# cn7macropad.net
KiCad netlist of a schematic drawn in EAGLE
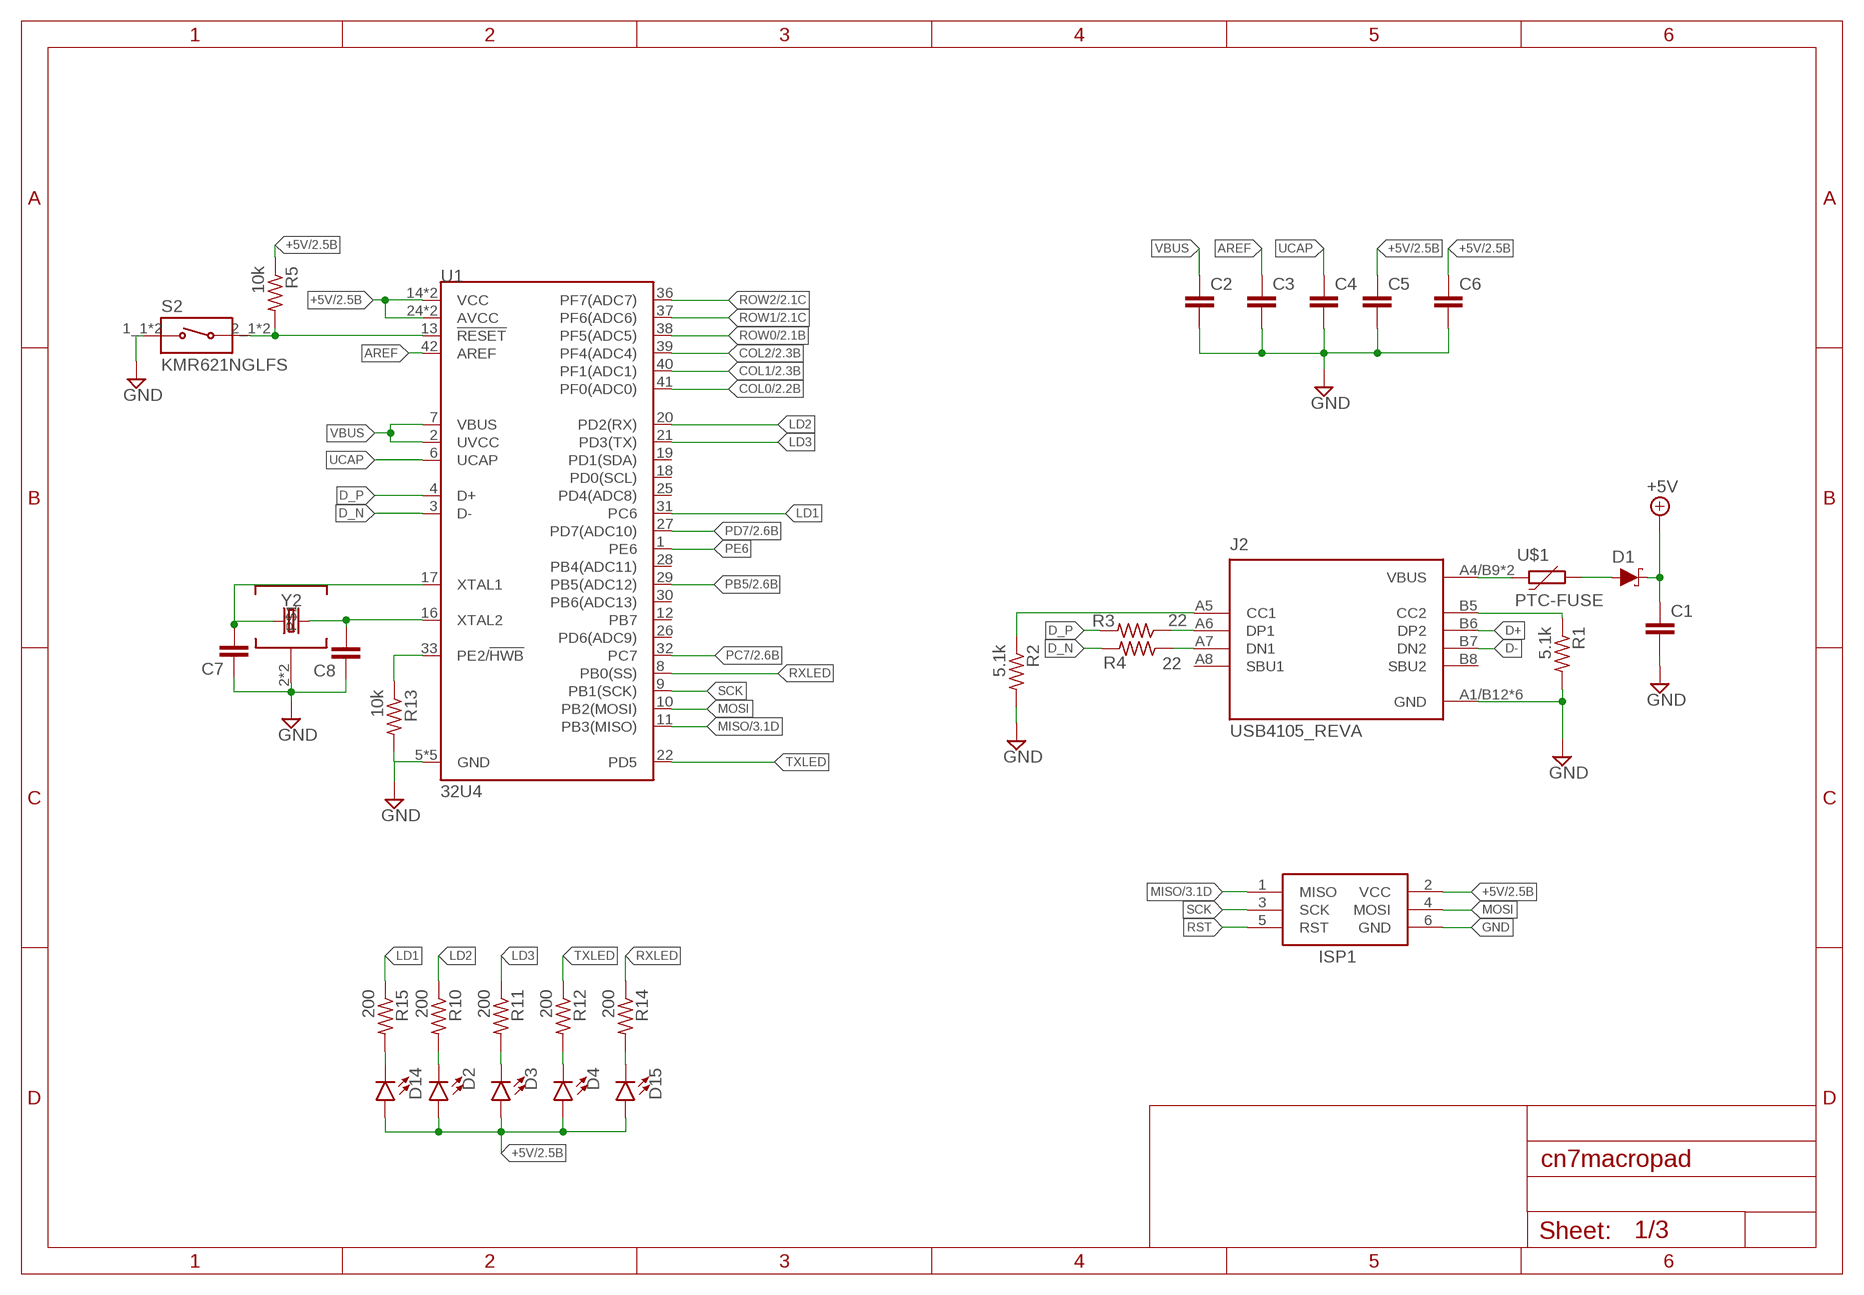
[diagram p0: schematic, sheet 1]
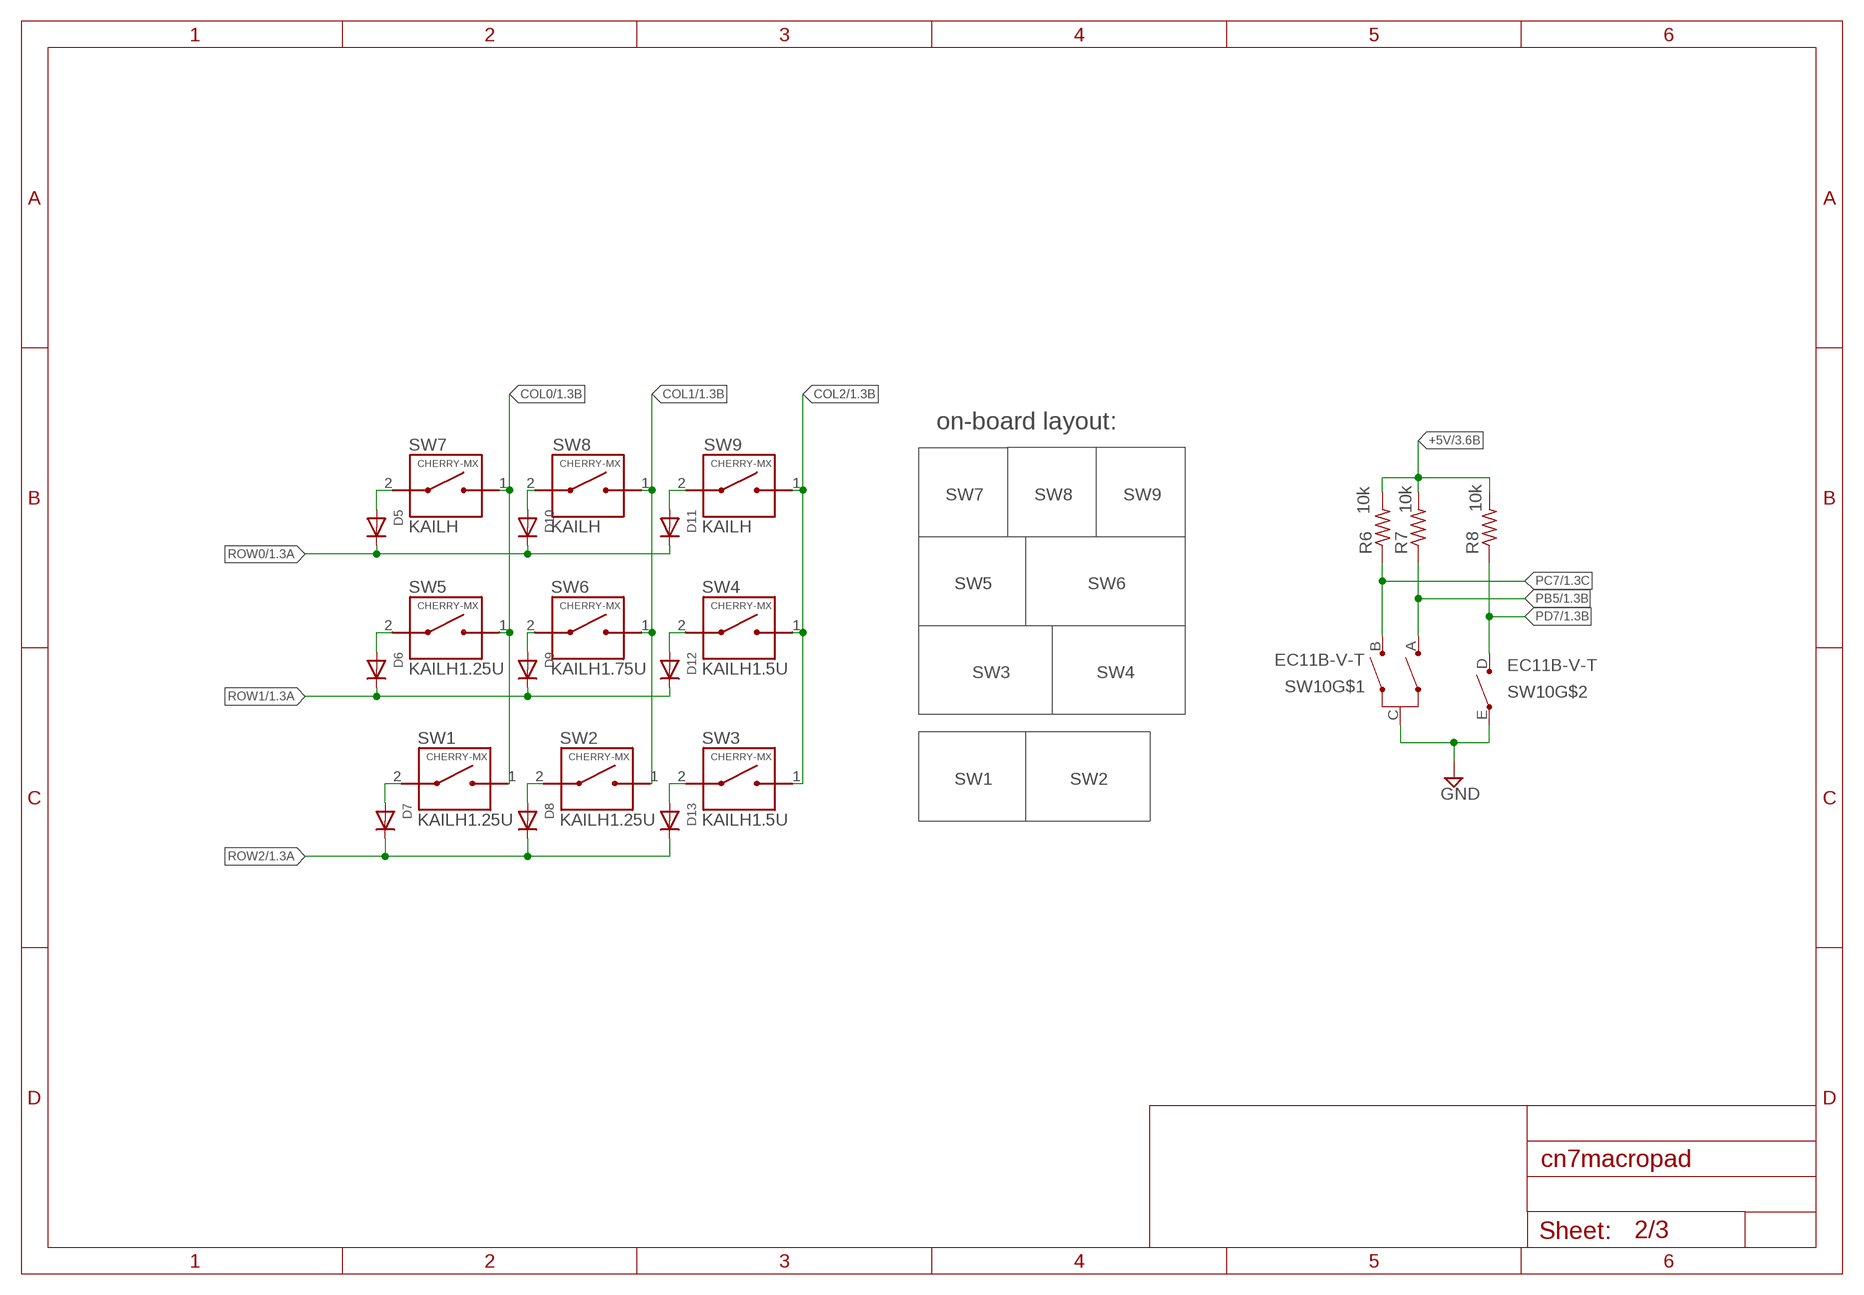
[diagram p1: schematic, sheet 2]
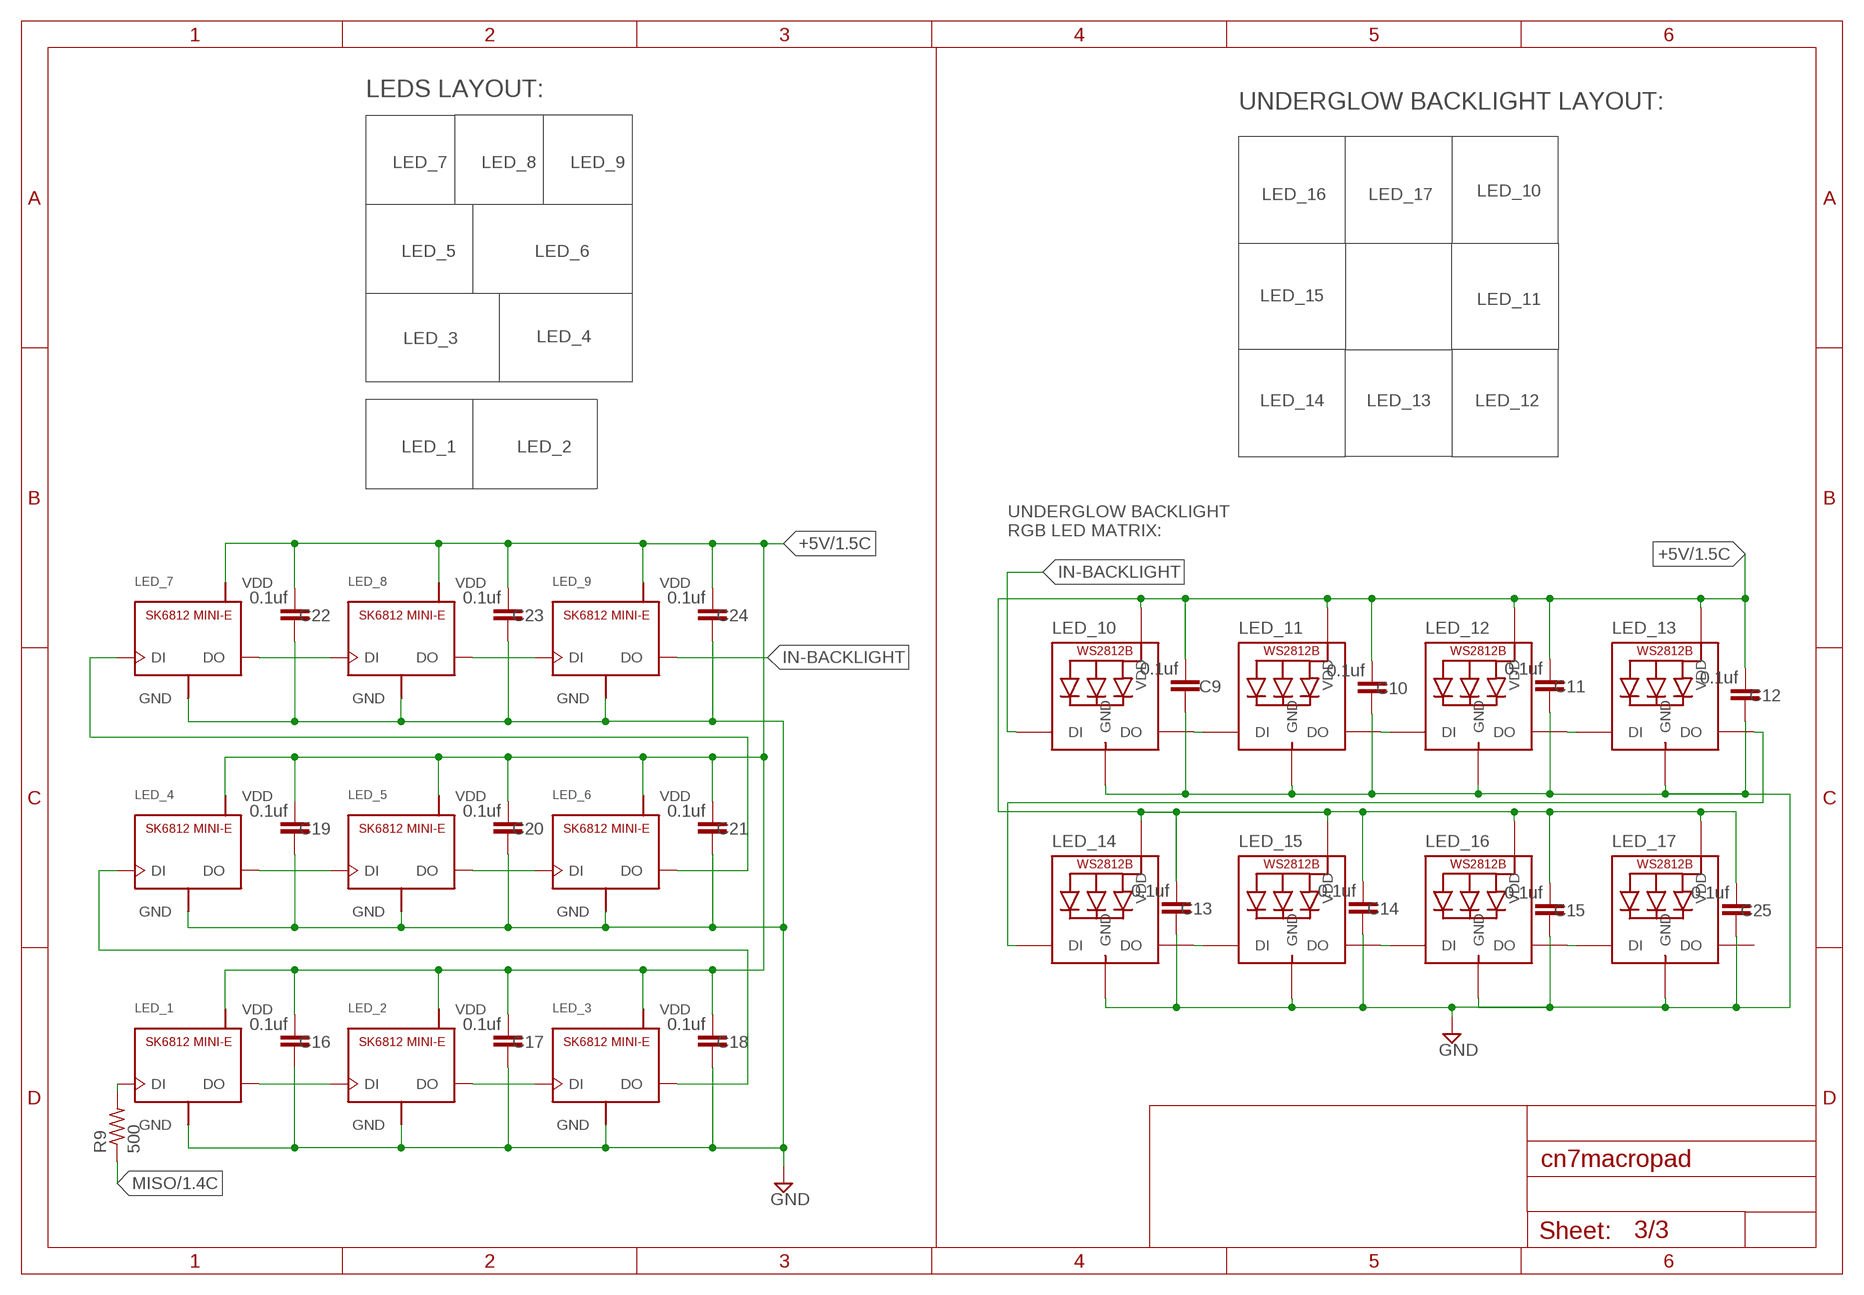
[diagram p2: schematic, sheet 3]

(export (version "E")
  (design (tool "Eeschema 10.0.6"))
  (components
    (comp (ref "C9")
      (value "0.1uf")
      (footprint "eagle-import:0603")
      (libsource (lib "eagle-import") (part "CAP-0603-50V-5%"))
    )
    (comp (ref "C10")
      (value "0.1uf")
      (footprint "eagle-import:0603")
      (libsource (lib "eagle-import") (part "CAP-0603-50V-5%"))
    )
    (comp (ref "C11")
      (value "0.1uf")
      (footprint "eagle-import:0603")
      (libsource (lib "eagle-import") (part "CAP-0603-50V-5%"))
    )
    (comp (ref "C12")
      (value "0.1uf")
      (footprint "eagle-import:0603")
      (libsource (lib "eagle-import") (part "CAP-0603-50V-5%"))
    )
    (comp (ref "C13")
      (value "0.1uf")
      (footprint "eagle-import:0603")
      (libsource (lib "eagle-import") (part "CAP-0603-50V-5%"))
    )
    (comp (ref "C14")
      (value "0.1uf")
      (footprint "eagle-import:0603")
      (libsource (lib "eagle-import") (part "CAP-0603-50V-5%"))
    )
    (comp (ref "C15")
      (value "0.1uf")
      (footprint "eagle-import:0603")
      (libsource (lib "eagle-import") (part "CAP-0603-50V-5%"))
    )
    (comp (ref "C16")
      (value "0.1uf")
      (footprint "eagle-import:0603")
      (libsource (lib "eagle-import") (part "CAP-0603-50V-5%"))
    )
    (comp (ref "C17")
      (value "0.1uf")
      (footprint "eagle-import:0603")
      (libsource (lib "eagle-import") (part "CAP-0603-50V-5%"))
    )
    (comp (ref "C18")
      (value "0.1uf")
      (footprint "eagle-import:0603")
      (libsource (lib "eagle-import") (part "CAP-0603-50V-5%"))
    )
    (comp (ref "C19")
      (value "0.1uf")
      (footprint "eagle-import:0603")
      (libsource (lib "eagle-import") (part "CAP-0603-50V-5%"))
    )
    (comp (ref "C20")
      (value "0.1uf")
      (footprint "eagle-import:0603")
      (libsource (lib "eagle-import") (part "CAP-0603-50V-5%"))
    )
    (comp (ref "C21")
      (value "0.1uf")
      (footprint "eagle-import:0603")
      (libsource (lib "eagle-import") (part "CAP-0603-50V-5%"))
    )
    (comp (ref "C22")
      (value "0.1uf")
      (footprint "eagle-import:0603")
      (libsource (lib "eagle-import") (part "CAP-0603-50V-5%"))
    )
    (comp (ref "C23")
      (value "0.1uf")
      (footprint "eagle-import:0603")
      (libsource (lib "eagle-import") (part "CAP-0603-50V-5%"))
    )
    (comp (ref "C24")
      (value "0.1uf")
      (footprint "eagle-import:0603")
      (libsource (lib "eagle-import") (part "CAP-0603-50V-5%"))
    )
    (comp (ref "C25")
      (value "0.1uf")
      (footprint "eagle-import:0603")
      (libsource (lib "eagle-import") (part "CAP-0603-50V-5%"))
    )
    (comp (ref "LED_1")
      (value "SK6812-MINI-ESW")
      (footprint "eagle-import:SK6812-MINI-E")
      (libsource (lib "eagle-import") (part "SK6812-MINI-ESW"))
    )
    (comp (ref "LED_2")
      (value "SK6812-MINI-ESW")
      (footprint "eagle-import:SK6812-MINI-E")
      (libsource (lib "eagle-import") (part "SK6812-MINI-ESW"))
    )
    (comp (ref "LED_3")
      (value "SK6812-MINI-ESW")
      (footprint "eagle-import:SK6812-MINI-E")
      (libsource (lib "eagle-import") (part "SK6812-MINI-ESW"))
    )
    (comp (ref "LED_4")
      (value "SK6812-MINI-ESW")
      (footprint "eagle-import:SK6812-MINI-E")
      (libsource (lib "eagle-import") (part "SK6812-MINI-ESW"))
    )
    (comp (ref "LED_5")
      (value "SK6812-MINI-ESW")
      (footprint "eagle-import:SK6812-MINI-E")
      (libsource (lib "eagle-import") (part "SK6812-MINI-ESW"))
    )
    (comp (ref "LED_6")
      (value "SK6812-MINI-ESW")
      (footprint "eagle-import:SK6812-MINI-E")
      (libsource (lib "eagle-import") (part "SK6812-MINI-ESW"))
    )
    (comp (ref "LED_7")
      (value "SK6812-MINI-ESW")
      (footprint "eagle-import:SK6812-MINI-E")
      (libsource (lib "eagle-import") (part "SK6812-MINI-ESW"))
    )
    (comp (ref "LED_8")
      (value "SK6812-MINI-ESW")
      (footprint "eagle-import:SK6812-MINI-E")
      (libsource (lib "eagle-import") (part "SK6812-MINI-ESW"))
    )
    (comp (ref "LED_9")
      (value "SK6812-MINI-ESW")
      (footprint "eagle-import:SK6812-MINI-E")
      (libsource (lib "eagle-import") (part "SK6812-MINI-ESW"))
    )
    (comp (ref "LED_10")
      (value "WS2812B5050")
      (footprint "eagle-import:WS2812B")
      (fields (field (name "SPICEPREFIX") "E"))
      (libsource (lib "eagle-import") (part "WS2812B5050"))
    )
    (comp (ref "LED_11")
      (value "WS2812B5050")
      (footprint "eagle-import:WS2812B")
      (libsource (lib "eagle-import") (part "WS2812B5050"))
    )
    (comp (ref "LED_12")
      (value "WS2812B5050")
      (footprint "eagle-import:WS2812B")
      (libsource (lib "eagle-import") (part "WS2812B5050"))
    )
    (comp (ref "LED_13")
      (value "WS2812B5050")
      (footprint "eagle-import:WS2812B")
      (libsource (lib "eagle-import") (part "WS2812B5050"))
    )
    (comp (ref "LED_14")
      (value "WS2812B5050")
      (footprint "eagle-import:WS2812B")
      (libsource (lib "eagle-import") (part "WS2812B5050"))
    )
    (comp (ref "LED_15")
      (value "WS2812B5050")
      (footprint "eagle-import:WS2812B")
      (libsource (lib "eagle-import") (part "WS2812B5050"))
    )
    (comp (ref "LED_16")
      (value "WS2812B5050")
      (footprint "eagle-import:WS2812B")
      (libsource (lib "eagle-import") (part "WS2812B5050"))
    )
    (comp (ref "LED_17")
      (value "WS2812B5050")
      (footprint "eagle-import:WS2812B")
      (libsource (lib "eagle-import") (part "WS2812B5050"))
    )
    (comp (ref "R9")
      (value "500")
      (footprint "eagle-import:R0603")
      (libsource (lib "eagle-import") (part "RESISTORR0603"))
    )
    (comp (ref "D5")
      (value "DIODE")
      (footprint "eagle-import:SOD-523")
      (libsource (lib "eagle-import") (part "DIODE"))
    )
    (comp (ref "D6")
      (value "DIODE")
      (footprint "eagle-import:SOD-523")
      (libsource (lib "eagle-import") (part "DIODE"))
    )
    (comp (ref "D7")
      (value "DIODE")
      (footprint "eagle-import:SOD-523")
      (libsource (lib "eagle-import") (part "DIODE"))
    )
    (comp (ref "D8")
      (value "DIODE")
      (footprint "eagle-import:SOD-523")
      (libsource (lib "eagle-import") (part "DIODE"))
    )
    (comp (ref "D9")
      (value "DIODE")
      (footprint "eagle-import:SOD-523")
      (libsource (lib "eagle-import") (part "DIODE"))
    )
    (comp (ref "D10")
      (value "DIODE")
      (footprint "eagle-import:SOD-523")
      (libsource (lib "eagle-import") (part "DIODE"))
    )
    (comp (ref "D11")
      (value "DIODE")
      (footprint "eagle-import:SOD-523")
      (libsource (lib "eagle-import") (part "DIODE"))
    )
    (comp (ref "D12")
      (value "DIODESOD-523")
      (footprint "eagle-import:SOD-523")
      (libsource (lib "eagle-import") (part "DIODESOD-523"))
    )
    (comp (ref "D13")
      (value "DIODESOD-523")
      (footprint "eagle-import:SOD-523")
      (libsource (lib "eagle-import") (part "DIODESOD-523"))
    )
    (comp (ref "R6")
      (value "10k")
      (footprint "eagle-import:R0603")
      (libsource (lib "eagle-import") (part "RESISTORR0603"))
    )
    (comp (ref "R7")
      (value "10k")
      (footprint "eagle-import:R0603")
      (libsource (lib "eagle-import") (part "RESISTORR0603"))
    )
    (comp (ref "R8")
      (value "10k")
      (footprint "eagle-import:R0603")
      (libsource (lib "eagle-import") (part "RESISTORR0603"))
    )
    (comp (ref "SW1")
      (value "KAILH1.25U")
      (footprint "eagle-import:SWITCH_SOCKET-1.25U")
      (libsource (lib "eagle-import") (part "KAILH1.25U"))
    )
    (comp (ref "SW2")
      (value "KAILH1.25U")
      (footprint "eagle-import:SWITCH_SOCKET-1.25U")
      (libsource (lib "eagle-import") (part "KAILH1.25U"))
    )
    (comp (ref "SW3")
      (value "KAILH1.5U")
      (footprint "eagle-import:SWITCH_SOCKET-1.5U")
      (libsource (lib "eagle-import") (part "KAILH1.5U"))
    )
    (comp (ref "SW4")
      (value "KAILH1.5U")
      (footprint "eagle-import:SWITCH_SOCKET-1.5U")
      (libsource (lib "eagle-import") (part "KAILH1.5U"))
    )
    (comp (ref "SW5")
      (value "KAILH1.25U")
      (footprint "eagle-import:SWITCH_SOCKET-1.25U")
      (libsource (lib "eagle-import") (part "KAILH1.25U"))
    )
    (comp (ref "SW6")
      (value "KAILH1.75U")
      (footprint "eagle-import:SWITCH_SOCKET-1.75U")
      (libsource (lib "eagle-import") (part "KAILH1.75U"))
    )
    (comp (ref "SW7")
      (value "KAILH")
      (footprint "eagle-import:SWITCH_SOCKET-1U")
      (libsource (lib "eagle-import") (part "KAILH"))
    )
    (comp (ref "SW8")
      (value "KAILH")
      (footprint "eagle-import:SWITCH_SOCKET-1U")
      (libsource (lib "eagle-import") (part "KAILH"))
    )
    (comp (ref "SW9")
      (value "KAILH")
      (footprint "eagle-import:SWITCH_SOCKET-1U")
      (libsource (lib "eagle-import") (part "KAILH"))
    )
    (comp (ref "SW10")
      (value "EC11B-V-T")
      (footprint "eagle-import:EC11B-V")
      (libsource (lib "eagle-import") (part "EC11B-V-T"))
    )
    (comp (ref "C1")
      (value "10uF")
      (footprint "eagle-import:0603")
      (libsource (lib "eagle-import") (part "CAP-0603-50V-5%"))
    )
    (comp (ref "C2")
      (value "1.0uF")
      (footprint "eagle-import:0603")
      (libsource (lib "eagle-import") (part "CAP-0603-50V-5%"))
    )
    (comp (ref "C3")
      (value "1.0uF")
      (footprint "eagle-import:0603")
      (libsource (lib "eagle-import") (part "CAP-0603-50V-5%"))
    )
    (comp (ref "C4")
      (value "1.0uF")
      (footprint "eagle-import:0603")
      (libsource (lib "eagle-import") (part "CAP-0603-50V-5%"))
    )
    (comp (ref "C5")
      (value "1.0uF")
      (footprint "eagle-import:0603")
      (libsource (lib "eagle-import") (part "CAP-0603-50V-5%"))
    )
    (comp (ref "C6")
      (value "1.0uF")
      (footprint "eagle-import:0603")
      (libsource (lib "eagle-import") (part "CAP-0603-50V-5%"))
    )
    (comp (ref "C7")
      (value "22pF")
      (footprint "eagle-import:0603")
      (libsource (lib "eagle-import") (part "CAP-0603-50V-5%"))
    )
    (comp (ref "C8")
      (value "22pF")
      (footprint "eagle-import:0603")
      (libsource (lib "eagle-import") (part "CAP-0603-50V-5%"))
    )
    (comp (ref "D1")
      (value "3A/10V/280mV")
      (footprint "eagle-import:SOD-323")
      (libsource (lib "eagle-import") (part "DIODE-SCHOTTKY-BAT60A"))
    )
    (comp (ref "D2")
      (value "LED0603")
      (footprint "eagle-import:LED-0603")
      (libsource (lib "eagle-import") (part "LED0603"))
    )
    (comp (ref "D3")
      (value "LED0603")
      (footprint "eagle-import:LED-0603")
      (libsource (lib "eagle-import") (part "kailh_cn7_LED0603"))
    )
    (comp (ref "D4")
      (value "LED0603")
      (footprint "eagle-import:LED-0603")
      (libsource (lib "eagle-import") (part "kailh_cn7_LED0603"))
    )
    (comp (ref "D14")
      (value "LED0603")
      (footprint "eagle-import:LED-0603")
      (libsource (lib "eagle-import") (part "kailh_cn7_LED0603"))
    )
    (comp (ref "D15")
      (value "LED0603")
      (footprint "eagle-import:LED-0603")
      (libsource (lib "eagle-import") (part "kailh_cn7_LED0603"))
    )
    (comp (ref "ISP1")
      (value "AVRISP-6")
      (footprint "eagle-import:AVRISP")
      (libsource (lib "eagle-import") (part "AVRISP-6"))
    )
    (comp (ref "J2")
      (value "USB4105_REVA")
      (footprint "eagle-import:GCT_USB4105_REVA")
      (fields
        (field (name "DIGI-KEY_PART_NUMBER") "2073-USB4105-GF-ACT-ND")
        (field (name "MF") "Global Connector Technology")
        (field (name "MP") "USB4105")
      )
      (libsource (lib "eagle-import") (part "USB4105_REVA"))
    )
    (comp (ref "R1")
      (value "5.1k")
      (footprint "eagle-import:R0603")
      (libsource (lib "eagle-import") (part "RESISTORR0603"))
    )
    (comp (ref "R2")
      (value "5.1k")
      (footprint "eagle-import:R0603")
      (libsource (lib "eagle-import") (part "RESISTORR0603"))
    )
    (comp (ref "R3")
      (value "22")
      (footprint "eagle-import:R0603")
      (libsource (lib "eagle-import") (part "RESISTORR0603"))
    )
    (comp (ref "R4")
      (value "22")
      (footprint "eagle-import:R0603")
      (libsource (lib "eagle-import") (part "RESISTORR0603"))
    )
    (comp (ref "R5")
      (value "10k")
      (footprint "eagle-import:R0603")
      (libsource (lib "eagle-import") (part "RESISTORR0603"))
    )
    (comp (ref "R10")
      (value "200")
      (footprint "eagle-import:R0603")
      (libsource (lib "eagle-import") (part "RESISTORR0603"))
    )
    (comp (ref "R11")
      (value "200")
      (footprint "eagle-import:R0603")
      (libsource (lib "eagle-import") (part "RESISTORR0603"))
    )
    (comp (ref "R12")
      (value "200")
      (footprint "eagle-import:R0603")
      (libsource (lib "eagle-import") (part "RESISTORR0603"))
    )
    (comp (ref "R13")
      (value "10k")
      (footprint "eagle-import:R0603")
      (libsource (lib "eagle-import") (part "RESISTORR0603"))
    )
    (comp (ref "R14")
      (value "200")
      (footprint "eagle-import:R0603")
      (libsource (lib "eagle-import") (part "RESISTORR0603"))
    )
    (comp (ref "R15")
      (value "200")
      (footprint "eagle-import:R0603")
      (libsource (lib "eagle-import") (part "RESISTORR0603"))
    )
    (comp (ref "S2")
      (value "KMR621NGLFS")
      (footprint "eagle-import:SW_KMR621NGLFS")
      (fields
        (field (name "DIGI-KEY_PART_NUMBER") "CKN10684CT-ND")
        (field (name "MF") "C&K")
        (field (name "MP") "KMR621NG LFS")
      )
      (libsource (lib "eagle-import") (part "KMR621NGLFS"))
    )
    (comp (ref "U$1")
      (value "PTC-FUSE")
      (footprint "eagle-import:PTC1206")
      (libsource (lib "eagle-import") (part "PTC-FUSE"))
    )
    (comp (ref "U1")
      (value "32U4")
      (footprint "eagle-import:TQFP44")
      (libsource (lib "eagle-import") (part "ATMEGA32U4TQFP-44"))
    )
    (comp (ref "Y2")
      (value "CRYSTALSMD-3.2X2.5")
      (footprint "eagle-import:CRYSTAL-SMD-3.2X2.5MM")
      (libsource (lib "eagle-import") (part "CRYSTALSMD-3.2X2.5"))
    )
  )
  (nets
    (net (code "1") (name "+5V") (class "Default")
      (node (ref "C1") (pin "1") (pinfunction "1_1") (pintype "passive"))
      (node (ref "C10") (pin "2") (pinfunction "2_2") (pintype "passive"))
      (node (ref "C11") (pin "2") (pinfunction "2_2") (pintype "passive"))
      (node (ref "C12") (pin "2") (pinfunction "2_2") (pintype "passive"))
      (node (ref "C13") (pin "2") (pinfunction "2_2") (pintype "passive"))
      (node (ref "C14") (pin "2") (pinfunction "2_2") (pintype "passive"))
      (node (ref "C15") (pin "2") (pinfunction "2_2") (pintype "passive"))
      (node (ref "C16") (pin "2") (pinfunction "2_2") (pintype "passive"))
      (node (ref "C17") (pin "2") (pinfunction "2_2") (pintype "passive"))
      (node (ref "C18") (pin "2") (pinfunction "2_2") (pintype "passive"))
      (node (ref "C19") (pin "2") (pinfunction "2_2") (pintype "passive"))
      (node (ref "C20") (pin "2") (pinfunction "2_2") (pintype "passive"))
      (node (ref "C21") (pin "2") (pinfunction "2_2") (pintype "passive"))
      (node (ref "C22") (pin "2") (pinfunction "2_2") (pintype "passive"))
      (node (ref "C23") (pin "2") (pinfunction "2_2") (pintype "passive"))
      (node (ref "C24") (pin "2") (pinfunction "2_2") (pintype "passive"))
      (node (ref "C25") (pin "2") (pinfunction "2_2") (pintype "passive"))
      (node (ref "C5") (pin "1") (pinfunction "1_1") (pintype "passive"))
      (node (ref "C6") (pin "1") (pinfunction "1_1") (pintype "passive"))
      (node (ref "C9") (pin "2") (pinfunction "2_2") (pintype "passive"))
      (node (ref "D1") (pin "C") (pinfunction "C_C") (pintype "passive"))
      (node (ref "D14") (pin "A") (pinfunction "A_A") (pintype "passive"))
      (node (ref "D15") (pin "A") (pinfunction "A_A") (pintype "passive"))
      (node (ref "D2") (pin "A") (pinfunction "A_A") (pintype "passive"))
      (node (ref "D3") (pin "A") (pinfunction "A_A") (pintype "passive"))
      (node (ref "D4") (pin "A") (pinfunction "A_A") (pintype "passive"))
      (node (ref "ISP1") (pin "2") (pinfunction "VCC_2") (pintype "power_in"))
      (node (ref "LED_1") (pin "1-VDD") (pinfunction "VDD_1-VDD") (pintype "power_in"))
      (node (ref "LED_10") (pin "1-VDD") (pinfunction "VDD_1-VDD") (pintype "power_in"))
      (node (ref "LED_11") (pin "1-VDD") (pinfunction "VDD_1-VDD") (pintype "power_in"))
      (node (ref "LED_12") (pin "1-VDD") (pinfunction "VDD_1-VDD") (pintype "power_in"))
      (node (ref "LED_13") (pin "1-VDD") (pinfunction "VDD_1-VDD") (pintype "power_in"))
      (node (ref "LED_14") (pin "1-VDD") (pinfunction "VDD_1-VDD") (pintype "power_in"))
      (node (ref "LED_15") (pin "1-VDD") (pinfunction "VDD_1-VDD") (pintype "power_in"))
      (node (ref "LED_16") (pin "1-VDD") (pinfunction "VDD_1-VDD") (pintype "power_in"))
      (node (ref "LED_17") (pin "1-VDD") (pinfunction "VDD_1-VDD") (pintype "power_in"))
      (node (ref "LED_2") (pin "1-VDD") (pinfunction "VDD_1-VDD") (pintype "power_in"))
      (node (ref "LED_3") (pin "1-VDD") (pinfunction "VDD_1-VDD") (pintype "power_in"))
      (node (ref "LED_4") (pin "1-VDD") (pinfunction "VDD_1-VDD") (pintype "power_in"))
      (node (ref "LED_5") (pin "1-VDD") (pinfunction "VDD_1-VDD") (pintype "power_in"))
      (node (ref "LED_6") (pin "1-VDD") (pinfunction "VDD_1-VDD") (pintype "power_in"))
      (node (ref "LED_7") (pin "1-VDD") (pinfunction "VDD_1-VDD") (pintype "power_in"))
      (node (ref "LED_8") (pin "1-VDD") (pinfunction "VDD_1-VDD") (pintype "power_in"))
      (node (ref "LED_9") (pin "1-VDD") (pinfunction "VDD_1-VDD") (pintype "power_in"))
      (node (ref "R5") (pin "1") (pinfunction "1_1") (pintype "passive"))
      (node (ref "R6") (pin "2") (pinfunction "2_2") (pintype "passive"))
      (node (ref "R7") (pin "2") (pinfunction "2_2") (pintype "passive"))
      (node (ref "R8") (pin "2") (pinfunction "2_2") (pintype "passive"))
      (node (ref "U1") (pin "14") (pinfunction "VCC_14") (pintype "bidirectional"))
      (node (ref "U1") (pin "24") (pinfunction "AVCC_24") (pintype "bidirectional"))
      (node (ref "U1") (pin "34") (pinfunction "VCC_34") (pintype "bidirectional"))
      (node (ref "U1") (pin "44") (pinfunction "AVCC_44") (pintype "bidirectional"))
    )
    (net (code "2") (name "AREF") (class "Default")
      (node (ref "C3") (pin "1") (pinfunction "1_1") (pintype "passive"))
      (node (ref "U1") (pin "42") (pinfunction "AREF_42") (pintype "bidirectional"))
    )
    (net (code "3") (name "COL0") (class "Default")
      (node (ref "SW1") (pin "1") (pinfunction "2_1") (pintype "passive"))
      (node (ref "SW5") (pin "1") (pinfunction "2_1") (pintype "passive"))
      (node (ref "SW7") (pin "1") (pinfunction "2_1") (pintype "passive"))
      (node (ref "U1") (pin "41") (pinfunction "PF0(ADC0)_41") (pintype "bidirectional"))
    )
    (net (code "4") (name "COL1") (class "Default")
      (node (ref "SW2") (pin "1") (pinfunction "2_1") (pintype "passive"))
      (node (ref "SW6") (pin "1") (pinfunction "2_1") (pintype "passive"))
      (node (ref "SW8") (pin "1") (pinfunction "2_1") (pintype "passive"))
      (node (ref "U1") (pin "40") (pinfunction "PF1(ADC1)_40") (pintype "bidirectional"))
    )
    (net (code "5") (name "COL2") (class "Default")
      (node (ref "SW3") (pin "1") (pinfunction "2_1") (pintype "passive"))
      (node (ref "SW4") (pin "1") (pinfunction "2_1") (pintype "passive"))
      (node (ref "SW9") (pin "1") (pinfunction "2_1") (pintype "passive"))
      (node (ref "U1") (pin "39") (pinfunction "PF4(ADC4)_39") (pintype "bidirectional"))
    )
    (net (code "6") (name "D+") (class "Default")
      (node (ref "J2") (pin "A6") (pinfunction "DP1_A6") (pintype "bidirectional"))
      (node (ref "J2") (pin "B6") (pinfunction "DP2_B6") (pintype "bidirectional"))
      (node (ref "R3") (pin "1") (pinfunction "1_1") (pintype "passive"))
    )
    (net (code "7") (name "D-") (class "Default")
      (node (ref "J2") (pin "A7") (pinfunction "DN1_A7") (pintype "bidirectional"))
      (node (ref "J2") (pin "B7") (pinfunction "DN2_B7") (pintype "bidirectional"))
      (node (ref "R4") (pin "1") (pinfunction "1_1") (pintype "passive"))
    )
    (net (code "8") (name "D_N") (class "Default")
      (node (ref "R4") (pin "2") (pinfunction "2_2") (pintype "passive"))
      (node (ref "U1") (pin "3") (pinfunction "D-_3") (pintype "bidirectional"))
    )
    (net (code "9") (name "D_P") (class "Default")
      (node (ref "R3") (pin "2") (pinfunction "2_2") (pintype "passive"))
      (node (ref "U1") (pin "4") (pinfunction "D+_4") (pintype "bidirectional"))
    )
    (net (code "10") (name "GND") (class "Default")
      (node (ref "C1") (pin "2") (pinfunction "2_2") (pintype "passive"))
      (node (ref "C10") (pin "1") (pinfunction "1_1") (pintype "passive"))
      (node (ref "C11") (pin "1") (pinfunction "1_1") (pintype "passive"))
      (node (ref "C12") (pin "1") (pinfunction "1_1") (pintype "passive"))
      (node (ref "C13") (pin "1") (pinfunction "1_1") (pintype "passive"))
      (node (ref "C14") (pin "1") (pinfunction "1_1") (pintype "passive"))
      (node (ref "C15") (pin "1") (pinfunction "1_1") (pintype "passive"))
      (node (ref "C16") (pin "1") (pinfunction "1_1") (pintype "passive"))
      (node (ref "C17") (pin "1") (pinfunction "1_1") (pintype "passive"))
      (node (ref "C18") (pin "1") (pinfunction "1_1") (pintype "passive"))
      (node (ref "C19") (pin "1") (pinfunction "1_1") (pintype "passive"))
      (node (ref "C2") (pin "2") (pinfunction "2_2") (pintype "passive"))
      (node (ref "C20") (pin "1") (pinfunction "1_1") (pintype "passive"))
      (node (ref "C21") (pin "1") (pinfunction "1_1") (pintype "passive"))
      (node (ref "C22") (pin "1") (pinfunction "1_1") (pintype "passive"))
      (node (ref "C23") (pin "1") (pinfunction "1_1") (pintype "passive"))
      (node (ref "C24") (pin "1") (pinfunction "1_1") (pintype "passive"))
      (node (ref "C25") (pin "1") (pinfunction "1_1") (pintype "passive"))
      (node (ref "C3") (pin "2") (pinfunction "2_2") (pintype "passive"))
      (node (ref "C4") (pin "2") (pinfunction "2_2") (pintype "passive"))
      (node (ref "C5") (pin "2") (pinfunction "2_2") (pintype "passive"))
      (node (ref "C6") (pin "2") (pinfunction "2_2") (pintype "passive"))
      (node (ref "C7") (pin "1") (pinfunction "1_1") (pintype "passive"))
      (node (ref "C8") (pin "1") (pinfunction "1_1") (pintype "passive"))
      (node (ref "C9") (pin "1") (pinfunction "1_1") (pintype "passive"))
      (node (ref "ISP1") (pin "6") (pinfunction "GND_6") (pintype "power_in"))
      (node (ref "J2") (pin "A1/B12") (pinfunction "GND_A1/B12") (pintype "power_in"))
      (node (ref "J2") (pin "B1/A12") (pinfunction "GND_B1/A12") (pintype "power_in"))
      (node (ref "J2") (pin "G1") (pinfunction "GND_G1") (pintype "power_in"))
      (node (ref "J2") (pin "G2") (pinfunction "GND_G2") (pintype "power_in"))
      (node (ref "J2") (pin "G3") (pinfunction "GND_G3") (pintype "power_in"))
      (node (ref "J2") (pin "G4") (pinfunction "GND_G4") (pintype "power_in"))
      (node (ref "LED_1") (pin "3-GND") (pinfunction "GND_3-GND") (pintype "power_in"))
      (node (ref "LED_10") (pin "3-GND") (pinfunction "GND_3-GND") (pintype "power_in"))
      (node (ref "LED_11") (pin "3-GND") (pinfunction "GND_3-GND") (pintype "power_in"))
      (node (ref "LED_12") (pin "3-GND") (pinfunction "GND_3-GND") (pintype "power_in"))
      (node (ref "LED_13") (pin "3-GND") (pinfunction "GND_3-GND") (pintype "power_in"))
      (node (ref "LED_14") (pin "3-GND") (pinfunction "GND_3-GND") (pintype "power_in"))
      (node (ref "LED_15") (pin "3-GND") (pinfunction "GND_3-GND") (pintype "power_in"))
      (node (ref "LED_16") (pin "3-GND") (pinfunction "GND_3-GND") (pintype "power_in"))
      (node (ref "LED_17") (pin "3-GND") (pinfunction "GND_3-GND") (pintype "power_in"))
      (node (ref "LED_2") (pin "3-GND") (pinfunction "GND_3-GND") (pintype "power_in"))
      (node (ref "LED_3") (pin "3-GND") (pinfunction "GND_3-GND") (pintype "power_in"))
      (node (ref "LED_4") (pin "3-GND") (pinfunction "GND_3-GND") (pintype "power_in"))
      (node (ref "LED_5") (pin "3-GND") (pinfunction "GND_3-GND") (pintype "power_in"))
      (node (ref "LED_6") (pin "3-GND") (pinfunction "GND_3-GND") (pintype "power_in"))
      (node (ref "LED_7") (pin "3-GND") (pinfunction "GND_3-GND") (pintype "power_in"))
      (node (ref "LED_8") (pin "3-GND") (pinfunction "GND_3-GND") (pintype "power_in"))
      (node (ref "LED_9") (pin "3-GND") (pinfunction "GND_3-GND") (pintype "power_in"))
      (node (ref "R1") (pin "2") (pinfunction "2_2") (pintype "passive"))
      (node (ref "R13") (pin "2") (pinfunction "2_2") (pintype "passive"))
      (node (ref "R2") (pin "2") (pinfunction "2_2") (pintype "passive"))
      (node (ref "S2") (pin "1_1") (pinfunction "1_1_1") (pintype "passive"))
      (node (ref "S2") (pin "1_2") (pinfunction "1_1_2") (pintype "passive"))
      (node (ref "SW10") (pin "C") (pinfunction "C_C") (pintype "passive"))
      (node (ref "SW10") (pin "E") (pinfunction "E_E") (pintype "passive"))
      (node (ref "U1") (pin "15") (pinfunction "GND_15") (pintype "bidirectional"))
      (node (ref "U1") (pin "23") (pinfunction "GND_23") (pintype "bidirectional"))
      (node (ref "U1") (pin "35") (pinfunction "GND_35") (pintype "bidirectional"))
      (node (ref "U1") (pin "43") (pinfunction "GND_43") (pintype "bidirectional"))
      (node (ref "U1") (pin "5") (pinfunction "GND_5") (pintype "bidirectional"))
      (node (ref "Y2") (pin "2") (pinfunction "P$1_2") (pintype "bidirectional"))
      (node (ref "Y2") (pin "4") (pinfunction "P$1_4") (pintype "bidirectional"))
    )
    (net (code "11") (name "IN-BACKLIGHT") (class "Default")
      (node (ref "LED_10") (pin "4-DIN") (pinfunction "DI_4-DIN") (pintype "input"))
      (node (ref "LED_9") (pin "2-DOUT") (pinfunction "DO_2-DOUT") (pintype "output"))
    )
    (net (code "12") (name "LD1") (class "Default")
      (node (ref "R15") (pin "1") (pinfunction "1_1") (pintype "passive"))
      (node (ref "U1") (pin "31") (pinfunction "PC6_31") (pintype "bidirectional"))
    )
    (net (code "13") (name "LD2") (class "Default")
      (node (ref "R10") (pin "1") (pinfunction "1_1") (pintype "passive"))
      (node (ref "U1") (pin "20") (pinfunction "PD2(RX)_20") (pintype "bidirectional"))
    )
    (net (code "14") (name "LD3") (class "Default")
      (node (ref "R11") (pin "1") (pinfunction "1_1") (pintype "passive"))
      (node (ref "U1") (pin "21") (pinfunction "PD3(TX)_21") (pintype "bidirectional"))
    )
    (net (code "15") (name "MISO") (class "Default")
      (node (ref "ISP1") (pin "1") (pinfunction "MISO_1") (pintype "input"))
      (node (ref "R9") (pin "1") (pinfunction "1_1") (pintype "passive"))
      (node (ref "U1") (pin "11") (pinfunction "PB3(MISO)_11") (pintype "bidirectional"))
    )
    (net (code "16") (name "MOSI") (class "Default")
      (node (ref "ISP1") (pin "4") (pinfunction "MOSI_4") (pintype "output"))
      (node (ref "U1") (pin "10") (pinfunction "PB2(MOSI)_10") (pintype "bidirectional"))
    )
    (net (code "17") (name "Net-(D1-PadA)") (class "Default")
      (node (ref "D1") (pin "A") (pinfunction "A_A") (pintype "passive"))
      (node (ref "U$1") (pin "2") (pinfunction "2_2") (pintype "passive"))
    )
    (net (code "18") (name "Net-(D2-PadC)") (class "Default")
      (node (ref "D2") (pin "C") (pinfunction "C_C") (pintype "passive"))
      (node (ref "R10") (pin "2") (pinfunction "2_2") (pintype "passive"))
    )
    (net (code "19") (name "Net-(D3-PadC)") (class "Default")
      (node (ref "D3") (pin "C") (pinfunction "C_C") (pintype "passive"))
      (node (ref "R11") (pin "2") (pinfunction "2_2") (pintype "passive"))
    )
    (net (code "20") (name "Net-(D4-PadC)") (class "Default")
      (node (ref "D4") (pin "C") (pinfunction "C_C") (pintype "passive"))
      (node (ref "R12") (pin "2") (pinfunction "2_2") (pintype "passive"))
    )
    (net (code "21") (name "Net-(D14-PadC)") (class "Default")
      (node (ref "D14") (pin "C") (pinfunction "C_C") (pintype "passive"))
      (node (ref "R15") (pin "2") (pinfunction "2_2") (pintype "passive"))
    )
    (net (code "22") (name "Net-(D15-PadC)") (class "Default")
      (node (ref "D15") (pin "C") (pinfunction "C_C") (pintype "passive"))
      (node (ref "R14") (pin "2") (pinfunction "2_2") (pintype "passive"))
    )
    (net (code "23") (name "Net-(J2-CC1)") (class "Default")
      (node (ref "J2") (pin "A5") (pinfunction "CC1_A5") (pintype "bidirectional"))
      (node (ref "R2") (pin "1") (pinfunction "1_1") (pintype "passive"))
    )
    (net (code "24") (name "Net-(J2-CC2)") (class "Default")
      (node (ref "J2") (pin "B5") (pinfunction "CC2_B5") (pintype "bidirectional"))
      (node (ref "R1") (pin "1") (pinfunction "1_1") (pintype "passive"))
    )
    (net (code "25") (name "Net-(LED_1-DI)") (class "Default")
      (node (ref "LED_1") (pin "4-DIN") (pinfunction "DI_4-DIN") (pintype "input"))
      (node (ref "R9") (pin "2") (pinfunction "2_2") (pintype "passive"))
    )
    (net (code "26") (name "Net-(LED_1-DO)") (class "Default")
      (node (ref "LED_1") (pin "2-DOUT") (pinfunction "DO_2-DOUT") (pintype "output"))
      (node (ref "LED_2") (pin "4-DIN") (pinfunction "DI_4-DIN") (pintype "input"))
    )
    (net (code "27") (name "Net-(LED_2-DO)") (class "Default")
      (node (ref "LED_2") (pin "2-DOUT") (pinfunction "DO_2-DOUT") (pintype "output"))
      (node (ref "LED_3") (pin "4-DIN") (pinfunction "DI_4-DIN") (pintype "input"))
    )
    (net (code "28") (name "Net-(LED_3-DO)") (class "Default")
      (node (ref "LED_3") (pin "2-DOUT") (pinfunction "DO_2-DOUT") (pintype "output"))
      (node (ref "LED_4") (pin "4-DIN") (pinfunction "DI_4-DIN") (pintype "input"))
    )
    (net (code "29") (name "Net-(LED_4-DO)") (class "Default")
      (node (ref "LED_4") (pin "2-DOUT") (pinfunction "DO_2-DOUT") (pintype "output"))
      (node (ref "LED_5") (pin "4-DIN") (pinfunction "DI_4-DIN") (pintype "input"))
    )
    (net (code "30") (name "Net-(LED_5-DO)") (class "Default")
      (node (ref "LED_5") (pin "2-DOUT") (pinfunction "DO_2-DOUT") (pintype "output"))
      (node (ref "LED_6") (pin "4-DIN") (pinfunction "DI_4-DIN") (pintype "input"))
    )
    (net (code "31") (name "Net-(LED_6-DO)") (class "Default")
      (node (ref "LED_6") (pin "2-DOUT") (pinfunction "DO_2-DOUT") (pintype "output"))
      (node (ref "LED_7") (pin "4-DIN") (pinfunction "DI_4-DIN") (pintype "input"))
    )
    (net (code "32") (name "Net-(LED_7-DO)") (class "Default")
      (node (ref "LED_7") (pin "2-DOUT") (pinfunction "DO_2-DOUT") (pintype "output"))
      (node (ref "LED_8") (pin "4-DIN") (pinfunction "DI_4-DIN") (pintype "input"))
    )
    (net (code "33") (name "Net-(LED_8-DO)") (class "Default")
      (node (ref "LED_8") (pin "2-DOUT") (pinfunction "DO_2-DOUT") (pintype "output"))
      (node (ref "LED_9") (pin "4-DIN") (pinfunction "DI_4-DIN") (pintype "input"))
    )
    (net (code "34") (name "Net-(LED_10-DO)") (class "Default")
      (node (ref "LED_10") (pin "2-DOUT") (pinfunction "DO_2-DOUT") (pintype "output"))
      (node (ref "LED_11") (pin "4-DIN") (pinfunction "DI_4-DIN") (pintype "input"))
    )
    (net (code "35") (name "Net-(LED_11-DO)") (class "Default")
      (node (ref "LED_11") (pin "2-DOUT") (pinfunction "DO_2-DOUT") (pintype "output"))
      (node (ref "LED_12") (pin "4-DIN") (pinfunction "DI_4-DIN") (pintype "input"))
    )
    (net (code "36") (name "Net-(LED_12-DO)") (class "Default")
      (node (ref "LED_12") (pin "2-DOUT") (pinfunction "DO_2-DOUT") (pintype "output"))
      (node (ref "LED_13") (pin "4-DIN") (pinfunction "DI_4-DIN") (pintype "input"))
    )
    (net (code "37") (name "Net-(LED_13-DO)") (class "Default")
      (node (ref "LED_13") (pin "2-DOUT") (pinfunction "DO_2-DOUT") (pintype "output"))
      (node (ref "LED_14") (pin "4-DIN") (pinfunction "DI_4-DIN") (pintype "input"))
    )
    (net (code "38") (name "Net-(LED_14-DO)") (class "Default")
      (node (ref "LED_14") (pin "2-DOUT") (pinfunction "DO_2-DOUT") (pintype "output"))
      (node (ref "LED_15") (pin "4-DIN") (pinfunction "DI_4-DIN") (pintype "input"))
    )
    (net (code "39") (name "Net-(LED_15-DO)") (class "Default")
      (node (ref "LED_15") (pin "2-DOUT") (pinfunction "DO_2-DOUT") (pintype "output"))
      (node (ref "LED_16") (pin "4-DIN") (pinfunction "DI_4-DIN") (pintype "input"))
    )
    (net (code "40") (name "Net-(LED_16-DO)") (class "Default")
      (node (ref "LED_16") (pin "2-DOUT") (pinfunction "DO_2-DOUT") (pintype "output"))
      (node (ref "LED_17") (pin "4-DIN") (pinfunction "DI_4-DIN") (pintype "input"))
    )
    (net (code "41") (name "Net-(SW1-1)") (class "Default")
      (node (ref "D7") (pin "A") (pinfunction "A_A") (pintype "passive"))
      (node (ref "SW1") (pin "2") (pinfunction "1_2") (pintype "passive"))
    )
    (net (code "42") (name "Net-(SW2-1)") (class "Default")
      (node (ref "D8") (pin "A") (pinfunction "A_A") (pintype "passive"))
      (node (ref "SW2") (pin "2") (pinfunction "1_2") (pintype "passive"))
    )
    (net (code "43") (name "Net-(SW3-1)") (class "Default")
      (node (ref "D13") (pin "A") (pinfunction "A_A") (pintype "passive"))
      (node (ref "SW3") (pin "2") (pinfunction "1_2") (pintype "passive"))
    )
    (net (code "44") (name "Net-(SW4-1)") (class "Default")
      (node (ref "D12") (pin "A") (pinfunction "A_A") (pintype "passive"))
      (node (ref "SW4") (pin "2") (pinfunction "1_2") (pintype "passive"))
    )
    (net (code "45") (name "Net-(SW5-1)") (class "Default")
      (node (ref "D6") (pin "A") (pinfunction "A_A") (pintype "passive"))
      (node (ref "SW5") (pin "2") (pinfunction "1_2") (pintype "passive"))
    )
    (net (code "46") (name "Net-(SW6-1)") (class "Default")
      (node (ref "D9") (pin "A") (pinfunction "A_A") (pintype "passive"))
      (node (ref "SW6") (pin "2") (pinfunction "1_2") (pintype "passive"))
    )
    (net (code "47") (name "Net-(SW7-1)") (class "Default")
      (node (ref "D5") (pin "A") (pinfunction "A_A") (pintype "passive"))
      (node (ref "SW7") (pin "2") (pinfunction "1_2") (pintype "passive"))
    )
    (net (code "48") (name "Net-(SW8-1)") (class "Default")
      (node (ref "D10") (pin "A") (pinfunction "A_A") (pintype "passive"))
      (node (ref "SW8") (pin "2") (pinfunction "1_2") (pintype "passive"))
    )
    (net (code "49") (name "Net-(SW9-1)") (class "Default")
      (node (ref "D11") (pin "A") (pinfunction "A_A") (pintype "passive"))
      (node (ref "SW9") (pin "2") (pinfunction "1_2") (pintype "passive"))
    )
    (net (code "50") (name "Net-(U1-PE2{slash}~{HWB})") (class "Default")
      (node (ref "R13") (pin "1") (pinfunction "1_1") (pintype "passive"))
      (node (ref "U1") (pin "33") (pinfunction "PE2/~{HWB}_33") (pintype "bidirectional"))
    )
    (net (code "51") (name "Net-(U1-XTAL1)") (class "Default")
      (node (ref "C7") (pin "2") (pinfunction "2_2") (pintype "passive"))
      (node (ref "U1") (pin "17") (pinfunction "XTAL1_17") (pintype "bidirectional"))
      (node (ref "Y2") (pin "1") (pinfunction "1_1") (pintype "passive"))
    )
    (net (code "52") (name "Net-(U1-XTAL2)") (class "Default")
      (node (ref "C8") (pin "2") (pinfunction "2_2") (pintype "passive"))
      (node (ref "U1") (pin "16") (pinfunction "XTAL2_16") (pintype "bidirectional"))
      (node (ref "Y2") (pin "3") (pinfunction "2_3") (pintype "passive"))
    )
    (net (code "53") (name "PB5") (class "Default")
      (node (ref "R7") (pin "1") (pinfunction "1_1") (pintype "passive"))
      (node (ref "SW10") (pin "A") (pinfunction "A_A") (pintype "passive"))
      (node (ref "U1") (pin "29") (pinfunction "PB5(ADC12)_29") (pintype "bidirectional"))
    )
    (net (code "54") (name "PC7") (class "Default")
      (node (ref "R6") (pin "1") (pinfunction "1_1") (pintype "passive"))
      (node (ref "SW10") (pin "B") (pinfunction "B_B") (pintype "passive"))
      (node (ref "U1") (pin "32") (pinfunction "PC7_32") (pintype "bidirectional"))
    )
    (net (code "55") (name "PD7") (class "Default")
      (node (ref "R8") (pin "1") (pinfunction "1_1") (pintype "passive"))
      (node (ref "SW10") (pin "D") (pinfunction "D_D") (pintype "passive"))
      (node (ref "U1") (pin "27") (pinfunction "PD7(ADC10)_27") (pintype "bidirectional"))
    )
    (net (code "56") (name "PE6") (class "Default")
      (node (ref "U1") (pin "1") (pinfunction "PE6_1") (pintype "bidirectional"))
    )
    (net (code "57") (name "ROW0") (class "Default")
      (node (ref "D10") (pin "K") (pinfunction "C_K") (pintype "passive"))
      (node (ref "D11") (pin "K") (pinfunction "C_K") (pintype "passive"))
      (node (ref "D5") (pin "K") (pinfunction "C_K") (pintype "passive"))
      (node (ref "U1") (pin "38") (pinfunction "PF5(ADC5)_38") (pintype "bidirectional"))
    )
    (net (code "58") (name "ROW1") (class "Default")
      (node (ref "D12") (pin "K") (pinfunction "C_K") (pintype "passive"))
      (node (ref "D6") (pin "K") (pinfunction "C_K") (pintype "passive"))
      (node (ref "D9") (pin "K") (pinfunction "C_K") (pintype "passive"))
      (node (ref "U1") (pin "37") (pinfunction "PF6(ADC6)_37") (pintype "bidirectional"))
    )
    (net (code "59") (name "ROW2") (class "Default")
      (node (ref "D13") (pin "K") (pinfunction "C_K") (pintype "passive"))
      (node (ref "D7") (pin "K") (pinfunction "C_K") (pintype "passive"))
      (node (ref "D8") (pin "K") (pinfunction "C_K") (pintype "passive"))
      (node (ref "U1") (pin "36") (pinfunction "PF7(ADC7)_36") (pintype "bidirectional"))
    )
    (net (code "60") (name "RST") (class "Default")
      (node (ref "ISP1") (pin "5") (pinfunction "RST_5") (pintype "output"))
      (node (ref "R5") (pin "2") (pinfunction "2_2") (pintype "passive"))
      (node (ref "S2") (pin "2_1") (pinfunction "2_2_1") (pintype "passive"))
      (node (ref "S2") (pin "2_2") (pinfunction "2_2_2") (pintype "passive"))
      (node (ref "U1") (pin "13") (pinfunction "~{RESET}_13") (pintype "bidirectional"))
    )
    (net (code "61") (name "RXLED") (class "Default")
      (node (ref "R14") (pin "1") (pinfunction "1_1") (pintype "passive"))
      (node (ref "U1") (pin "8") (pinfunction "PB0(SS)_8") (pintype "bidirectional"))
    )
    (net (code "62") (name "SCK") (class "Default")
      (node (ref "ISP1") (pin "3") (pinfunction "SCK_3") (pintype "output"))
      (node (ref "U1") (pin "9") (pinfunction "PB1(SCK)_9") (pintype "bidirectional"))
    )
    (net (code "63") (name "TXLED") (class "Default")
      (node (ref "R12") (pin "1") (pinfunction "1_1") (pintype "passive"))
      (node (ref "U1") (pin "22") (pinfunction "PD5_22") (pintype "bidirectional"))
    )
    (net (code "64") (name "UCAP") (class "Default")
      (node (ref "C4") (pin "1") (pinfunction "1_1") (pintype "passive"))
      (node (ref "U1") (pin "6") (pinfunction "UCAP_6") (pintype "bidirectional"))
    )
    (net (code "65") (name "VBUS") (class "Default")
      (node (ref "C2") (pin "1") (pinfunction "1_1") (pintype "passive"))
      (node (ref "J2") (pin "A4/B9") (pinfunction "VBUS_A4/B9") (pintype "power_in"))
      (node (ref "J2") (pin "B4/A9") (pinfunction "VBUS_B4/A9") (pintype "power_in"))
      (node (ref "U$1") (pin "1") (pinfunction "1_1") (pintype "passive"))
      (node (ref "U1") (pin "2") (pinfunction "UVCC_2") (pintype "bidirectional"))
      (node (ref "U1") (pin "7") (pinfunction "VBUS_7") (pintype "bidirectional"))
    )
    (net (code "66") (name "unconnected-(J2-SBU1-PadA8)") (class "Default")
      (node (ref "J2") (pin "A8") (pinfunction "SBU1_A8") (pintype "bidirectional"))
    )
    (net (code "67") (name "unconnected-(J2-SBU2-PadB8)") (class "Default")
      (node (ref "J2") (pin "B8") (pinfunction "SBU2_B8") (pintype "bidirectional"))
    )
    (net (code "68") (name "unconnected-(LED_17-DO-Pad2-DOUT)") (class "Default")
      (node (ref "LED_17") (pin "2-DOUT") (pinfunction "DO_2-DOUT") (pintype "output"))
    )
    (net (code "69") (name "unconnected-(U1-PB4(ADC11)-Pad28)") (class "Default")
      (node (ref "U1") (pin "28") (pinfunction "PB4(ADC11)_28") (pintype "bidirectional"))
    )
    (net (code "70") (name "unconnected-(U1-PB6(ADC13)-Pad30)") (class "Default")
      (node (ref "U1") (pin "30") (pinfunction "PB6(ADC13)_30") (pintype "bidirectional"))
    )
    (net (code "71") (name "unconnected-(U1-PB7-Pad12)") (class "Default")
      (node (ref "U1") (pin "12") (pinfunction "PB7_12") (pintype "bidirectional"))
    )
    (net (code "72") (name "unconnected-(U1-PD0(SCL)-Pad18)") (class "Default")
      (node (ref "U1") (pin "18") (pinfunction "PD0(SCL)_18") (pintype "bidirectional"))
    )
    (net (code "73") (name "unconnected-(U1-PD1(SDA)-Pad19)") (class "Default")
      (node (ref "U1") (pin "19") (pinfunction "PD1(SDA)_19") (pintype "bidirectional"))
    )
    (net (code "74") (name "unconnected-(U1-PD4(ADC8)-Pad25)") (class "Default")
      (node (ref "U1") (pin "25") (pinfunction "PD4(ADC8)_25") (pintype "bidirectional"))
    )
    (net (code "75") (name "unconnected-(U1-PD6(ADC9)-Pad26)") (class "Default")
      (node (ref "U1") (pin "26") (pinfunction "PD6(ADC9)_26") (pintype "bidirectional"))
    )
  )
)
